# hs-256-expansion-uphone.net
KiCad netlist of a schematic drawn in EAGLE
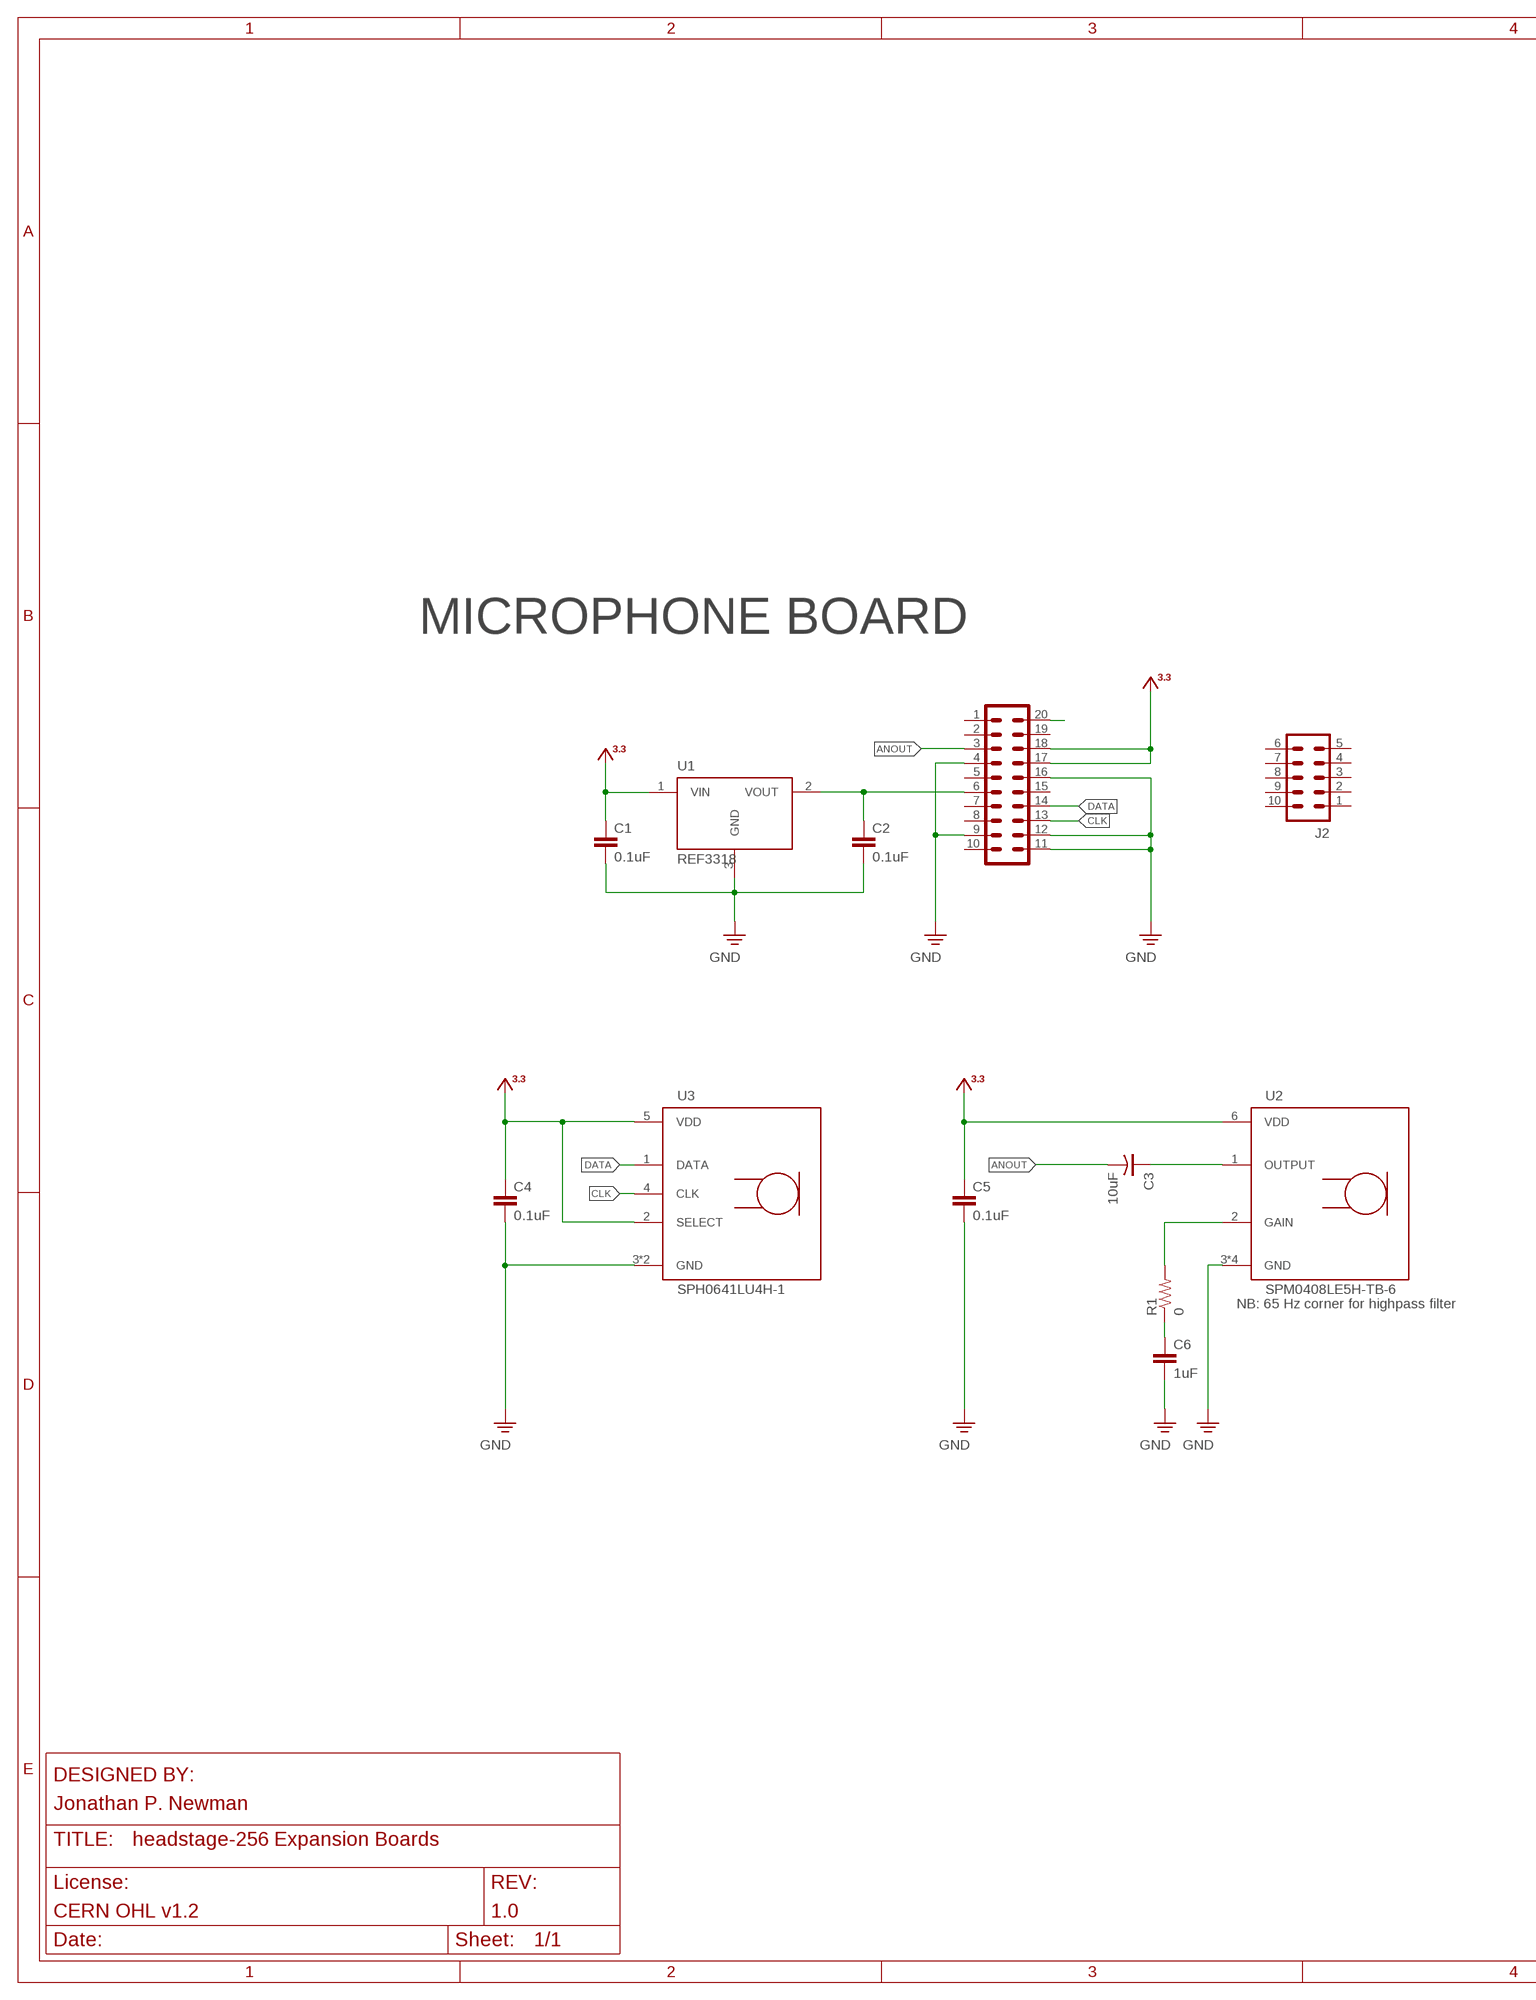
[diagram p0: schematic, sheet 1, part 1 of 2]
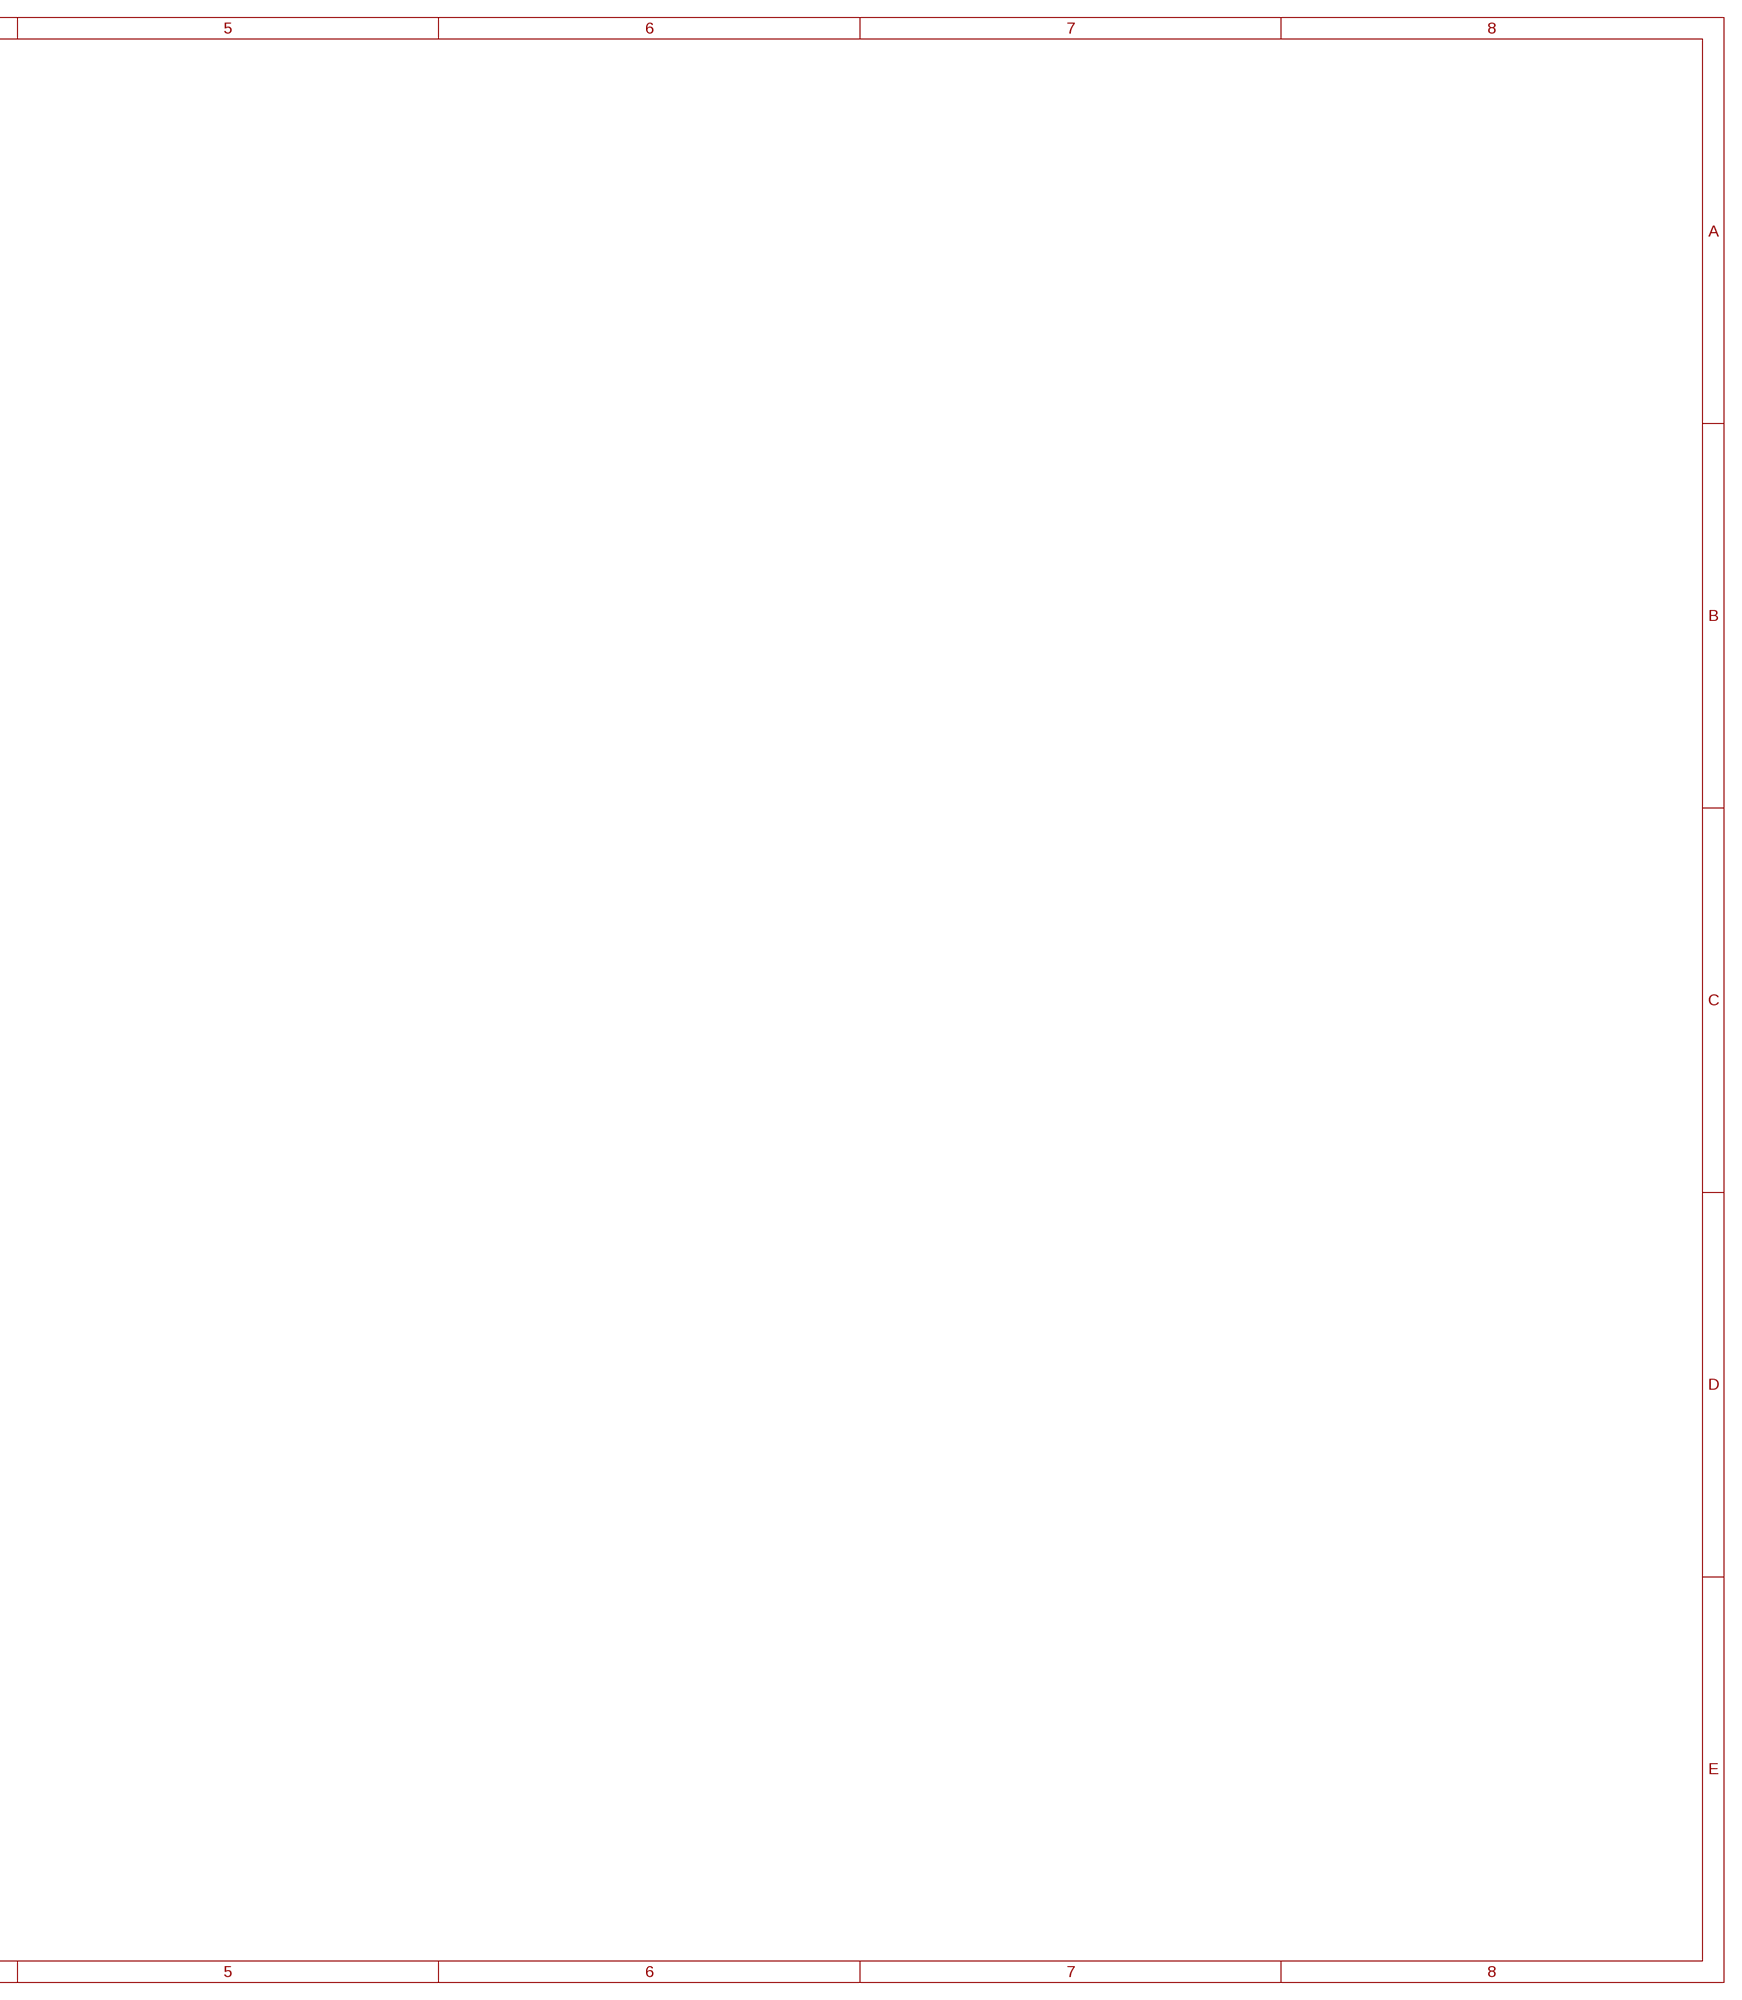
[diagram p1: schematic, sheet 1, part 2 of 2]

(export (version "E")
  (design (tool "Eeschema 10.0.6"))
  (components
    (comp (ref "C1")
      (value "0.1uF")
      (footprint "eagle-import:0402")
      (libsource (lib "eagle-import") (part "C_0402"))
    )
    (comp (ref "C2")
      (value "0.1uF")
      (footprint "eagle-import:0402")
      (libsource (lib "eagle-import") (part "C_0402"))
    )
    (comp (ref "C3")
      (value "10uF")
      (footprint "eagle-import:0805-POL")
      (libsource (lib "eagle-import") (part "C-POL_0805"))
    )
    (comp (ref "C4")
      (value "0.1uF")
      (footprint "eagle-import:0402")
      (libsource (lib "eagle-import") (part "C_0402"))
    )
    (comp (ref "C5")
      (value "0.1uF")
      (footprint "eagle-import:0402")
      (libsource (lib "eagle-import") (part "C_0402"))
    )
    (comp (ref "C6")
      (value "1uF")
      (footprint "eagle-import:0402")
      (libsource (lib "eagle-import") (part "C_0402"))
    )
    (comp (ref "J1")
      (value "PINHD-2X10_DF40-20REC")
      (footprint "eagle-import:DF40-20REC")
      (libsource (lib "eagle-import") (part "PINHD-2X10_DF40-20REC"))
    )
    (comp (ref "J2")
      (value "PINHD-2X5_DF40-REC")
      (footprint "eagle-import:DF40-10REC")
      (libsource (lib "eagle-import") (part "PINHD-2X5_DF40-REC"))
    )
    (comp (ref "R1")
      (value "0")
      (footprint "eagle-import:0402")
      (libsource (lib "eagle-import") (part "R_0402"))
    )
    (comp (ref "U1")
      (value "REF3318")
      (footprint "eagle-import:SOT23")
      (libsource (lib "eagle-import") (part "VREF_SOT"))
    )
    (comp (ref "U2")
      (value "SPM0408LE5H-TB-6")
      (footprint "eagle-import:KNOWLES-SPM")
      (libsource (lib "eagle-import") (part "MICROPHONE-AN_SPM"))
    )
    (comp (ref "U3")
      (value "SPH0641LU4H-1")
      (footprint "eagle-import:KNOWLES-SPH")
      (libsource (lib "eagle-import") (part "MICROPHONE-PCM_SPH"))
    )
  )
  (nets
    (net (code "1") (name "+3V3") (class "Default")
      (node (ref "C1") (pin "1") (pinfunction "1_1") (pintype "passive"))
      (node (ref "C4") (pin "1") (pinfunction "1_1") (pintype "passive"))
      (node (ref "C5") (pin "1") (pinfunction "1_1") (pintype "passive"))
      (node (ref "J1") (pin "17") (pinfunction "17_17") (pintype "bidirectional"))
      (node (ref "J1") (pin "18") (pinfunction "18_18") (pintype "bidirectional"))
      (node (ref "U1") (pin "1") (pinfunction "VIN_1") (pintype "input"))
      (node (ref "U2") (pin "6") (pinfunction "VDD_6") (pintype "power_in"))
      (node (ref "U3") (pin "2") (pinfunction "SELECT_2") (pintype "input"))
      (node (ref "U3") (pin "5") (pinfunction "VDD_5") (pintype "bidirectional"))
    )
    (net (code "2") (name "ANOUT") (class "Default")
      (node (ref "C3") (pin "C") (pinfunction "-_C") (pintype "passive"))
      (node (ref "J1") (pin "3") (pinfunction "3_3") (pintype "bidirectional"))
    )
    (net (code "3") (name "CLK") (class "Default")
      (node (ref "J1") (pin "13") (pinfunction "13_13") (pintype "bidirectional"))
      (node (ref "U3") (pin "4") (pinfunction "CLK_4") (pintype "input"))
    )
    (net (code "4") (name "DATA") (class "Default")
      (node (ref "J1") (pin "14") (pinfunction "14_14") (pintype "bidirectional"))
      (node (ref "U3") (pin "1") (pinfunction "DATA_1") (pintype "output"))
    )
    (net (code "5") (name "GND") (class "Default")
      (node (ref "C1") (pin "2") (pinfunction "2_2") (pintype "passive"))
      (node (ref "C2") (pin "2") (pinfunction "2_2") (pintype "passive"))
      (node (ref "C4") (pin "2") (pinfunction "2_2") (pintype "passive"))
      (node (ref "C5") (pin "2") (pinfunction "2_2") (pintype "passive"))
      (node (ref "C6") (pin "2") (pinfunction "2_2") (pintype "passive"))
      (node (ref "J1") (pin "11") (pinfunction "11_11") (pintype "bidirectional"))
      (node (ref "J1") (pin "12") (pinfunction "12_12") (pintype "bidirectional"))
      (node (ref "J1") (pin "16") (pinfunction "16_16") (pintype "bidirectional"))
      (node (ref "J1") (pin "4") (pinfunction "4_4") (pintype "bidirectional"))
      (node (ref "J1") (pin "9") (pinfunction "9_9") (pintype "bidirectional"))
      (node (ref "U1") (pin "3") (pinfunction "GND_3") (pintype "power_in"))
      (node (ref "U2") (pin "3") (pinfunction "GND_3") (pintype "power_in"))
      (node (ref "U2") (pin "4") (pinfunction "GND_4") (pintype "power_in"))
      (node (ref "U2") (pin "5") (pinfunction "GND_5") (pintype "power_in"))
      (node (ref "U2") (pin "7") (pinfunction "GND_7") (pintype "power_in"))
      (node (ref "U3") (pin "3") (pinfunction "GND_3") (pintype "bidirectional"))
      (node (ref "U3") (pin "6") (pinfunction "GND_6") (pintype "bidirectional"))
    )
    (net (code "6") (name "Net-(C3-+)") (class "Default")
      (node (ref "C3") (pin "A") (pinfunction "+_A") (pintype "passive"))
      (node (ref "U2") (pin "1") (pinfunction "OUTPUT_1") (pintype "output"))
    )
    (net (code "7") (name "Net-(C6-Pad1)") (class "Default")
      (node (ref "C6") (pin "1") (pinfunction "1_1") (pintype "passive"))
      (node (ref "R1") (pin "1") (pinfunction "1_1") (pintype "passive"))
    )
    (net (code "8") (name "Net-(U1-VOUT)") (class "Default")
      (node (ref "C2") (pin "1") (pinfunction "1_1") (pintype "passive"))
      (node (ref "J1") (pin "6") (pinfunction "6_6") (pintype "bidirectional"))
      (node (ref "U1") (pin "2") (pinfunction "VOUT_2") (pintype "output"))
    )
    (net (code "9") (name "Net-(U2-GAIN)") (class "Default")
      (node (ref "R1") (pin "2") (pinfunction "2_2") (pintype "passive"))
      (node (ref "U2") (pin "2") (pinfunction "GAIN_2") (pintype "input"))
    )
    (net (code "10") (name "unconnected-(J1-Pad1)") (class "Default")
      (node (ref "J1") (pin "1") (pinfunction "1_1") (pintype "bidirectional"))
    )
    (net (code "11") (name "unconnected-(J1-Pad2)") (class "Default")
      (node (ref "J1") (pin "2") (pinfunction "2_2") (pintype "bidirectional"))
    )
    (net (code "12") (name "unconnected-(J1-Pad5)") (class "Default")
      (node (ref "J1") (pin "5") (pinfunction "5_5") (pintype "bidirectional"))
    )
    (net (code "13") (name "unconnected-(J1-Pad7)") (class "Default")
      (node (ref "J1") (pin "7") (pinfunction "7_7") (pintype "bidirectional"))
    )
    (net (code "14") (name "unconnected-(J1-Pad8)") (class "Default")
      (node (ref "J1") (pin "8") (pinfunction "8_8") (pintype "bidirectional"))
    )
    (net (code "15") (name "unconnected-(J1-Pad10)") (class "Default")
      (node (ref "J1") (pin "10") (pinfunction "10_10") (pintype "bidirectional"))
    )
    (net (code "16") (name "unconnected-(J1-Pad15)") (class "Default")
      (node (ref "J1") (pin "15") (pinfunction "15_15") (pintype "bidirectional"))
    )
    (net (code "17") (name "unconnected-(J1-Pad19)") (class "Default")
      (node (ref "J1") (pin "19") (pinfunction "19_19") (pintype "bidirectional"))
    )
    (net (code "18") (name "unconnected-(J1-Pad20)") (class "Default")
      (node (ref "J1") (pin "20") (pinfunction "20_20") (pintype "bidirectional"))
    )
    (net (code "19") (name "unconnected-(J2-2-Pad10)") (class "Default")
      (node (ref "J2") (pin "10") (pinfunction "2_10") (pintype "passive"))
    )
    (net (code "20") (name "unconnected-(J2-3-Pad2)") (class "Default")
      (node (ref "J2") (pin "2") (pinfunction "3_2") (pintype "passive"))
    )
    (net (code "21") (name "unconnected-(J2-4-Pad9)") (class "Default")
      (node (ref "J2") (pin "9") (pinfunction "4_9") (pintype "passive"))
    )
    (net (code "22") (name "unconnected-(J2-5-Pad3)") (class "Default")
      (node (ref "J2") (pin "3") (pinfunction "5_3") (pintype "passive"))
    )
    (net (code "23") (name "unconnected-(J2-6-Pad8)") (class "Default")
      (node (ref "J2") (pin "8") (pinfunction "6_8") (pintype "passive"))
    )
    (net (code "24") (name "unconnected-(J2-7-Pad4)") (class "Default")
      (node (ref "J2") (pin "4") (pinfunction "7_4") (pintype "passive"))
    )
    (net (code "25") (name "unconnected-(J2-8-Pad7)") (class "Default")
      (node (ref "J2") (pin "7") (pinfunction "8_7") (pintype "passive"))
    )
    (net (code "26") (name "unconnected-(J2-9-Pad5)") (class "Default")
      (node (ref "J2") (pin "5") (pinfunction "9_5") (pintype "passive"))
    )
    (net (code "27") (name "unconnected-(J2-10-Pad6)") (class "Default")
      (node (ref "J2") (pin "6") (pinfunction "10_6") (pintype "passive"))
    )
    (net (code "28") (name "unconnected-(J2-Pad1)") (class "Default")
      (node (ref "J2") (pin "1") (pinfunction "1_1") (pintype "passive"))
    )
  )
)
